# DP_UART_RVA.net
KiCad netlist of a schematic drawn in Altium Designer
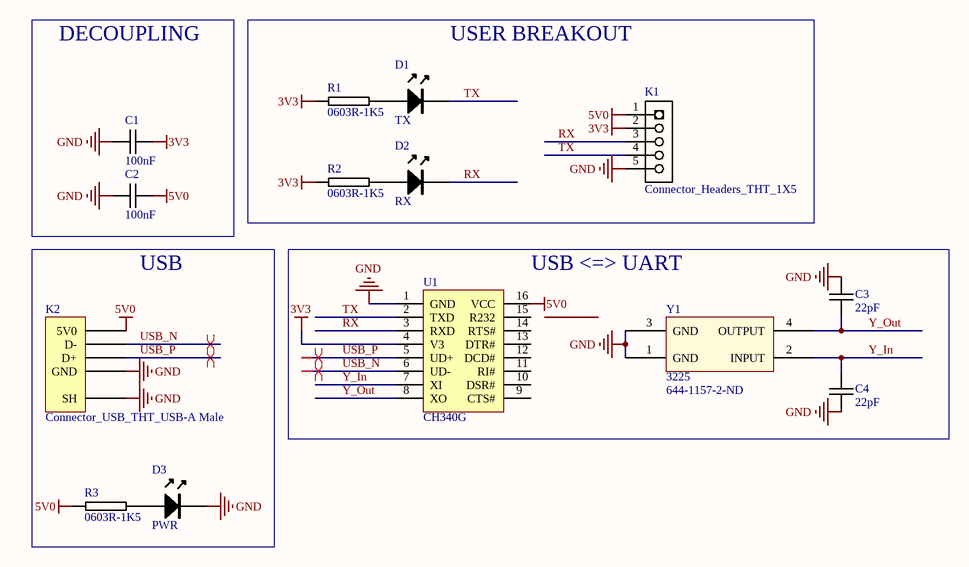
[diagram p0: DP_UART_RVA.SchDoc]

(export (version "E")
  (design (tool "Eeschema 10.0.6"))
  (components
    (comp (ref "C1")
      (value "100nF")
      (footprint "0603C-GENERIC")
      (description "CAPACITOR 0603 CERAMIC GENERIC")
      (libsource (lib "RVA_Altium_Library") (part "Passives_Capacitors_0603_GENERIC"))
    )
    (comp (ref "C2")
      (value "100nF")
      (footprint "0603C-GENERIC")
      (description "CAPACITOR 0603 CERAMIC GENERIC")
      (libsource (lib "RVA_Altium_Library") (part "Passives_Capacitors_0603_GENERIC"))
    )
    (comp (ref "C3")
      (value "22pF")
      (footprint "0603C-GENERIC")
      (description "CAPACITOR 0603 CERAMIC")
      (fields (field (name "TOLERANCE") "±5%") (field (name "MANUFACTURER PART NUMBER") "ECJ-1VC1H220J"))
      (libsource (lib "RVA_Altium_Library") (part "Passives_Capacitors_0603_22PF-50V-C0G-PAN"))
    )
    (comp (ref "C4")
      (value "22pF")
      (footprint "0603C-GENERIC")
      (description "CAPACITOR 0603 CERAMIC")
      (fields (field (name "TOLERANCE") "±5%") (field (name "MANUFACTURER PART NUMBER") "ECJ-1VC1H220J"))
      (libsource (lib "RVA_Altium_Library") (part "Passives_Capacitors_0603_22PF-50V-C0G-PAN"))
    )
    (comp (ref "D1")
      (value "TX")
      (footprint "0805LED")
      (libsource (lib "RVA_Altium_Library") (part "LED_SMD_0805"))
    )
    (comp (ref "D2")
      (value "RX")
      (footprint "0805LED")
      (libsource (lib "RVA_Altium_Library") (part "LED_SMD_0805"))
    )
    (comp (ref "D3")
      (value "PWR")
      (footprint "0805LED")
      (libsource (lib "RVA_Altium_Library") (part "LED_SMD_0805"))
    )
    (comp (ref "K1")
      (value "Connector_Headers_THT_1X5")
      (footprint "HEADER-1X5")
      (description "PINHEADER 1X5")
      (libsource (lib "RVA_Altium_Library") (part "Connector_Headers_THT_1X5"))
    )
    (comp (ref "K2")
      (value "Connector_USB_THT_USB-A Male")
      (footprint "USB-A - MALE")
      (libsource (lib "RVA_Connector_USB_THT") (part "Connector_USB_THT_USB-A Male"))
    )
    (comp (ref "R1")
      (value "0603R-1K5")
      (footprint "0603R-1k5")
      (description "GENERIC RESISTOR 0603")
      (fields (field (name "MANUFACTURER PART NUMBER") "RMCF 1/16 15K 1% R") (field (name "TOLERANCE") "±1%"))
      (libsource (lib "RVA_Passives_Resistors_0603") (part "0603R-1K5"))
    )
    (comp (ref "R2")
      (value "0603R-1K5")
      (footprint "0603R-1k5")
      (description "GENERIC RESISTOR 0603")
      (fields (field (name "MANUFACTURER PART NUMBER") "RMCF 1/16 15K 1% R") (field (name "TOLERANCE") "±1%"))
      (libsource (lib "RVA_Passives_Resistors_0603") (part "0603R-1K5"))
    )
    (comp (ref "R3")
      (value "0603R-1K5")
      (footprint "0603R-1k5")
      (description "GENERIC RESISTOR 0603")
      (fields (field (name "MANUFACTURER PART NUMBER") "RMCF 1/16 15K 1% R") (field (name "TOLERANCE") "±1%"))
      (libsource (lib "RVA_Passives_Resistors_0603") (part "0603R-1K5"))
    )
    (comp (ref "U1") (value "CH340G") (footprint "SO16") (libsource (lib "CH340") (part "CH340G")))
    (comp (ref "Y1")
      (value "3225")
      (footprint "XTAL 3225")
      (fields (field (name "SUPPLIER PART NUMBER 1") "644-1157-2-ND"))
      (libsource (lib "RVA_Reference_Crystal Oscillator_SMD") (part "3225 Quartz"))
    )
  )
  (nets
    (net (code "1") (name "/RX") (class "Default")
      (node (ref "D2") (pin "K") (pintype "passive"))
      (node (ref "K1") (pin "3") (pintype "passive"))
      (node (ref "U1") (pin "3") (pinfunction "RXD_3") (pintype "passive"))
    )
    (net (code "2") (name "/TX") (class "Default")
      (node (ref "D1") (pin "K") (pintype "passive"))
      (node (ref "K1") (pin "4") (pintype "passive"))
      (node (ref "U1") (pin "2") (pinfunction "TXD_2") (pintype "passive"))
    )
    (net (code "3") (name "/USB_N") (class "Default")
      (node (ref "K2") (pin "3") (pinfunction "D-_3") (pintype "passive"))
      (node (ref "U1") (pin "6") (pinfunction "UD-_6") (pintype "passive"))
    )
    (net (code "4") (name "/USB_P") (class "Default")
      (node (ref "K2") (pin "2") (pinfunction "D+_2") (pintype "passive"))
      (node (ref "U1") (pin "5") (pinfunction "UD+_5") (pintype "passive"))
    )
    (net (code "5") (name "/Y_In") (class "Default")
      (node (ref "C4") (pin "1") (pintype "passive"))
      (node (ref "U1") (pin "7") (pinfunction "XI_7") (pintype "passive"))
      (node (ref "Y1") (pin "2") (pinfunction "INPUT_2") (pintype "passive"))
    )
    (net (code "6") (name "/Y_Out") (class "Default")
      (node (ref "C3") (pin "2") (pintype "passive"))
      (node (ref "U1") (pin "8") (pinfunction "XO_8") (pintype "passive"))
      (node (ref "Y1") (pin "4") (pinfunction "OUTPUT_4") (pintype "passive"))
    )
    (net (code "7") (name "3V3") (class "Default")
      (node (ref "C1") (pin "2") (pintype "passive"))
      (node (ref "K1") (pin "2") (pintype "passive"))
      (node (ref "R1") (pin "1") (pintype "passive"))
      (node (ref "R2") (pin "1") (pintype "passive"))
      (node (ref "U1") (pin "4") (pinfunction "V3_4") (pintype "passive"))
    )
    (net (code "8") (name "5V0") (class "Default")
      (node (ref "C2") (pin "2") (pintype "passive"))
      (node (ref "K1") (pin "1") (pintype "passive"))
      (node (ref "K2") (pin "4") (pinfunction "5V0_4") (pintype "passive"))
      (node (ref "R3") (pin "1") (pintype "passive"))
      (node (ref "U1") (pin "16") (pinfunction "VCC_16") (pintype "passive"))
    )
    (net (code "9") (name "GND") (class "Default")
      (node (ref "C1") (pin "1") (pintype "passive"))
      (node (ref "C2") (pin "1") (pintype "passive"))
      (node (ref "C3") (pin "1") (pintype "passive"))
      (node (ref "C4") (pin "2") (pintype "passive"))
      (node (ref "D3") (pin "K") (pintype "passive"))
      (node (ref "K1") (pin "5") (pintype "passive"))
      (node (ref "K2") (pin "0") (pinfunction "SH_0") (pintype "passive"))
      (node (ref "K2") (pin "1") (pinfunction "GND_1") (pintype "passive"))
      (node (ref "U1") (pin "1") (pinfunction "GND_1") (pintype "passive"))
      (node (ref "Y1") (pin "1") (pinfunction "GND_1") (pintype "passive"))
      (node (ref "Y1") (pin "3") (pinfunction "GND_3") (pintype "passive"))
    )
    (net (code "10") (name "Net-(D1-PadA)") (class "Default")
      (node (ref "D1") (pin "A") (pintype "passive"))
      (node (ref "R1") (pin "2") (pintype "passive"))
    )
    (net (code "11") (name "Net-(D2-PadA)") (class "Default")
      (node (ref "D2") (pin "A") (pintype "passive"))
      (node (ref "R2") (pin "2") (pintype "passive"))
    )
    (net (code "12") (name "Net-(D3-PadA)") (class "Default")
      (node (ref "D3") (pin "A") (pintype "passive"))
      (node (ref "R3") (pin "2") (pintype "passive"))
    )
    (net (code "13") (name "unconnected-(U1-CTS#-Pad9)") (class "Default")
      (node (ref "U1") (pin "9") (pinfunction "CTS#_9") (pintype "passive"))
    )
    (net (code "14") (name "unconnected-(U1-DCD#-Pad12)") (class "Default")
      (node (ref "U1") (pin "12") (pinfunction "DCD#_12") (pintype "passive"))
    )
    (net (code "15") (name "unconnected-(U1-DSR#-Pad10)") (class "Default")
      (node (ref "U1") (pin "10") (pinfunction "DSR#_10") (pintype "passive"))
    )
    (net (code "16") (name "unconnected-(U1-DTR#-Pad13)") (class "Default")
      (node (ref "U1") (pin "13") (pinfunction "DTR#_13") (pintype "passive"))
    )
    (net (code "17") (name "unconnected-(U1-R232-Pad15)") (class "Default")
      (node (ref "U1") (pin "15") (pinfunction "R232_15") (pintype "passive"))
    )
    (net (code "18") (name "unconnected-(U1-RI#-Pad11)") (class "Default")
      (node (ref "U1") (pin "11") (pinfunction "RI#_11") (pintype "passive"))
    )
    (net (code "19") (name "unconnected-(U1-RTS#-Pad14)") (class "Default")
      (node (ref "U1") (pin "14") (pinfunction "RTS#_14") (pintype "passive"))
    )
  )
)
